# DISE_O_CON_3_3_Y_5_spi_separado_y_diodos.net
KiCad netlist of a schematic drawn in Altium Designer
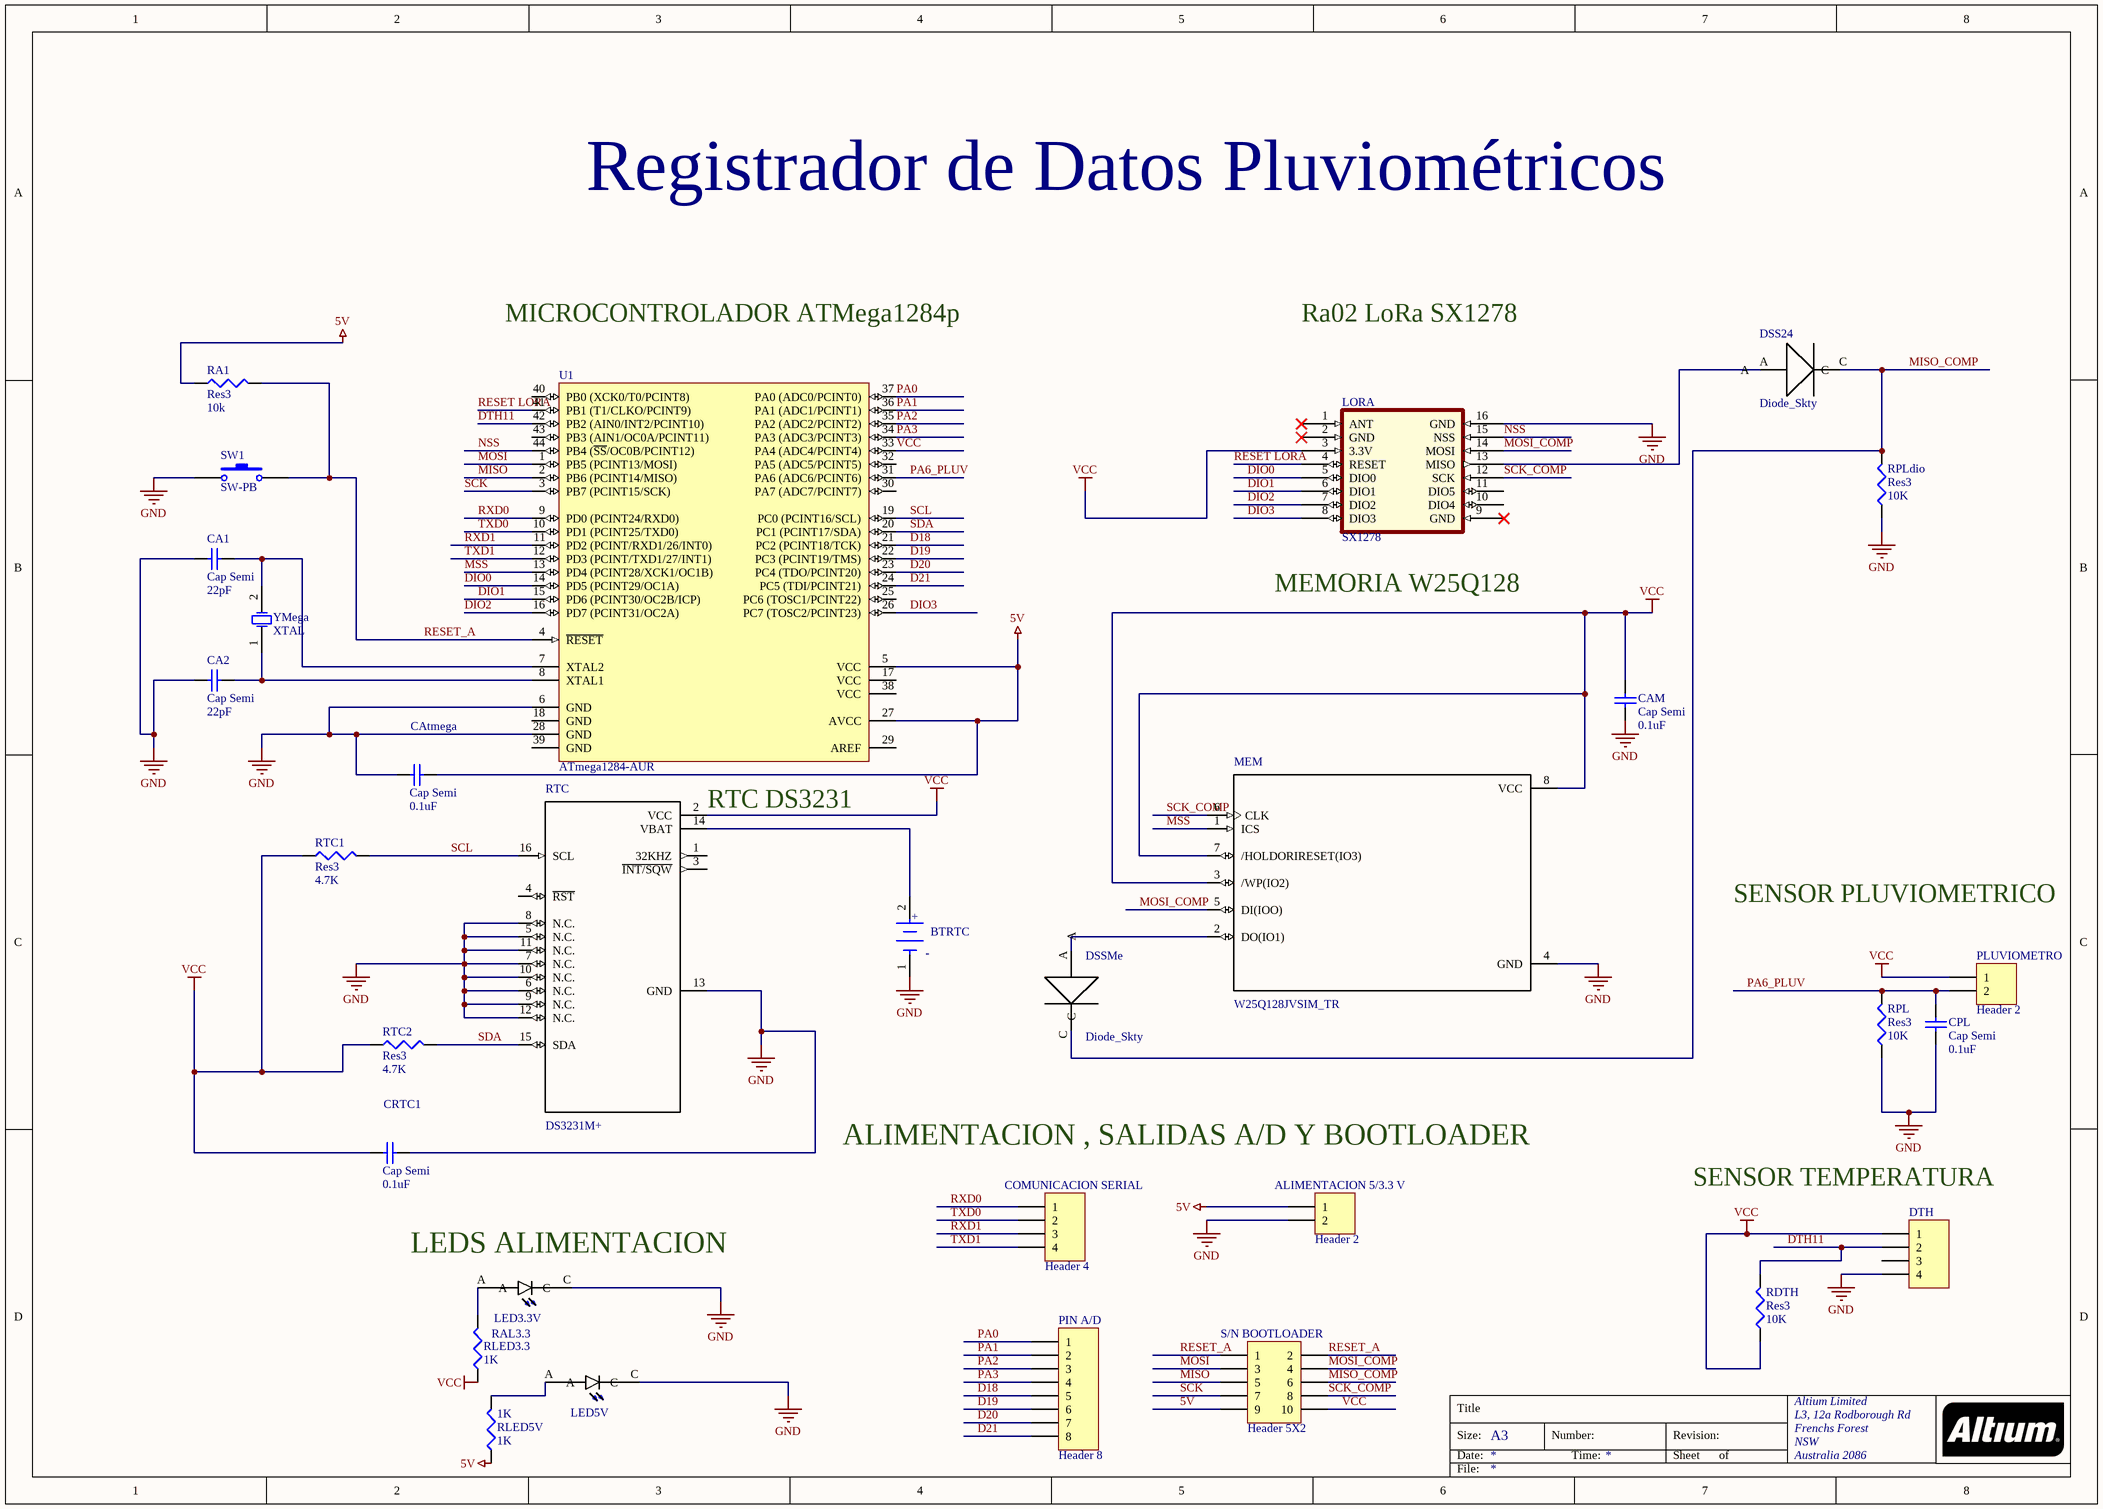
[diagram p0: DISEÑO CON 3.3 Y 5 spi separado y diodos.SchDoc]

(export (version "E")
  (design (tool "Eeschema 10.0.6"))
  (components
    (comp (ref "1K")
      (value "RLED5V")
      (footprint "6-0805_L")
      (description "Resistor")
      (fields (field (name "ALTIUM_VALUE") "1K") (field (name "PUBLISHER") "Altium Limited"))
      (libsource (lib "Miscellaneous Devices") (part "Res3"))
    )
    (comp (ref "ALIMENTACION 5/3.3 V")
      (value "Header 2")
      (footprint "HDR1X2")
      (description "Header, 2-Pin")
      (fields (field (name "PUBLISHER") "Altium Limited"))
      (libsource (lib "Miscellaneous Connectors") (part "Header 2"))
    )
    (comp (ref "BTRTC")
      (value "CR-1220-HFN")
      (footprint "Panasonic_CR-1220-HFN_MFG")
      (libsource (lib "Batt_Panasonic_CR-1220-HFN_eec") (part "CR-1220-HFN"))
    )
    (comp (ref "CA1")
      (value "Cap Semi")
      (footprint "C0805")
      (description "Capacitor (Semiconductor SIM Model)")
      (fields (field (name "ALTIUM_VALUE") "22pF") (field (name "PUBLISHER") "Altium Limited"))
      (libsource (lib "Miscellaneous Devices") (part "Cap Semi"))
    )
    (comp (ref "CA2")
      (value "Cap Semi")
      (footprint "C0805")
      (description "Capacitor (Semiconductor SIM Model)")
      (fields (field (name "ALTIUM_VALUE") "22pF") (field (name "PUBLISHER") "Altium Limited"))
      (libsource (lib "Miscellaneous Devices") (part "Cap Semi"))
    )
    (comp (ref "CAM")
      (value "Cap Semi")
      (footprint "C0805")
      (description "Capacitor (Semiconductor SIM Model)")
      (fields (field (name "ALTIUM_VALUE") "0.1uF") (field (name "PUBLISHER") "Altium Limited"))
      (libsource (lib "Miscellaneous Devices") (part "Cap Semi"))
    )
    (comp (ref "CAtmega")
      (value "Cap Semi")
      (footprint "C0805")
      (description "Capacitor (Semiconductor SIM Model)")
      (fields (field (name "ALTIUM_VALUE") "0.1uF") (field (name "PUBLISHER") "Altium Limited"))
      (libsource (lib "Miscellaneous Devices") (part "Cap Semi"))
    )
    (comp (ref "COMUNICACION SERIAL")
      (value "Header 4")
      (footprint "HDR1X4")
      (description "Header, 4-Pin")
      (fields (field (name "PUBLISHER") "Altium Limited"))
      (libsource (lib "Miscellaneous Connectors") (part "Header 4"))
    )
    (comp (ref "CPL")
      (value "Cap Semi")
      (footprint "C0805")
      (description "Capacitor (Semiconductor SIM Model)")
      (fields (field (name "ALTIUM_VALUE") "0.1uF") (field (name "PUBLISHER") "Altium Limited"))
      (libsource (lib "Miscellaneous Devices") (part "Cap Semi"))
    )
    (comp (ref "CRTC1")
      (value "Cap Semi")
      (footprint "C0805")
      (description "Capacitor (Semiconductor SIM Model)")
      (fields (field (name "ALTIUM_VALUE") "0.1uF") (field (name "PUBLISHER") "Altium Limited"))
      (libsource (lib "Miscellaneous Devices") (part "Cap Semi"))
    )
    (comp (ref "DSS24")
      (value "Diode_Skty")
      (footprint "*DIOM5436X247N")
      (libsource (lib "SS24_Real") (part "Component_1"))
    )
    (comp (ref "DSSMe")
      (value "Diode_Skty")
      (footprint "*DIOM5436X247N")
      (libsource (lib "SS24_Real") (part "Component_1"))
    )
    (comp (ref "DTH")
      (value "~")
      (footprint "HDR1X4")
      (description "Header, 4-Pin")
      (fields (field (name "PUBLISHER") "Altium Limited"))
      (libsource (lib "Miscellaneous Connectors") (part "Header 4"))
    )
    (comp (ref "LED3.3V")
      (value "~")
      (footprint "*LEDC2012X70N_598-8140-107F(Primary)")
      (description "Led; 0805 Smt Led, Yellow, Alingap, Water Clear Lens, 140 Deg Viewing Angle")
      (fields (field (name "MP") "598-8140-107F") (field (name "MF") "Dialight"))
      (libsource (lib "598-8140-107F") (part "598-8140-107F"))
    )
    (comp (ref "LED5V")
      (value "~")
      (footprint "*LEDC2012X70N_598-8140-107F(Primary)")
      (description "Led; 0805 Smt Led, Yellow, Alingap, Water Clear Lens, 140 Deg Viewing Angle")
      (fields (field (name "MP") "598-8140-107F") (field (name "MF") "Dialight"))
      (libsource (lib "598-8140-107F") (part "598-8140-107F"))
    )
    (comp (ref "LORA")
      (value "SX1278")
      (footprint "SOP200P1800X250-16N")
      (libsource (lib "LORA") (part "Component_1"))
    )
    (comp (ref "MEM")
      (value "W25Q128JVSIM_TR")
      (footprint "*SOIC127P790X216-8N")
      (description "Ic Flash 128mbit 133mhz 8soic")
      (fields (field (name "MP") "W25Q128JVSIM TR") (field (name "MF") "Winbond Electronics"))
      (libsource (lib "W25Q128JVSIM_TR") (part "W25Q128JVSIM_TR"))
    )
    (comp (ref "PIN A/D")
      (value "Header 8")
      (footprint "HDR1X8")
      (description "Header, 8-Pin")
      (fields (field (name "PUBLISHER") "Altium Limited"))
      (libsource (lib "Miscellaneous Connectors") (part "Header 8"))
    )
    (comp (ref "PLUVIOMETRO")
      (value "Header 2")
      (footprint "HDR1X2")
      (description "Header, 2-Pin")
      (fields (field (name "PUBLISHER") "Altium Limited"))
      (libsource (lib "Miscellaneous Connectors") (part "Header 2"))
    )
    (comp (ref "RA1")
      (value "Res3")
      (footprint "6-0805_L")
      (description "Resistor")
      (fields (field (name "ALTIUM_VALUE") "10k") (field (name "PUBLISHER") "Altium Limited"))
      (libsource (lib "Miscellaneous Devices") (part "Res3"))
    )
    (comp (ref "RAL3.3")
      (value "RLED3.3")
      (footprint "6-0805_L")
      (description "Resistor")
      (fields (field (name "ALTIUM_VALUE") "1K") (field (name "PUBLISHER") "Altium Limited"))
      (libsource (lib "Miscellaneous Devices") (part "Res3"))
    )
    (comp (ref "RDTH")
      (value "Res3")
      (footprint "6-0805_L")
      (description "Resistor")
      (fields (field (name "ALTIUM_VALUE") "10K") (field (name "PUBLISHER") "Altium Limited"))
      (libsource (lib "Miscellaneous Devices") (part "Res3"))
    )
    (comp (ref "RPL")
      (value "Res3")
      (footprint "6-0805_L")
      (description "Resistor")
      (fields (field (name "ALTIUM_VALUE") "10K") (field (name "PUBLISHER") "Altium Limited"))
      (libsource (lib "Miscellaneous Devices") (part "Res3"))
    )
    (comp (ref "RPLdio")
      (value "Res3")
      (footprint "6-0805_L")
      (description "Resistor")
      (fields (field (name "ALTIUM_VALUE") "10K") (field (name "PUBLISHER") "Altium Limited"))
      (libsource (lib "Miscellaneous Devices") (part "Res3"))
    )
    (comp (ref "RTC")
      (value "DS3231M+")
      (footprint "*SOIC127P1032X265-16N")
      (description "Ic Real Time Clock I2c 16soic - Ds3231m+")
      (fields (field (name "MF") "Maxim Integrated"))
      (libsource (lib "DS3231M_") (part "DS3231M+"))
    )
    (comp (ref "RTC1")
      (value "Res3")
      (footprint "6-0805_L")
      (description "Resistor")
      (fields (field (name "ALTIUM_VALUE") "4.7K") (field (name "PUBLISHER") "Altium Limited"))
      (libsource (lib "Miscellaneous Devices") (part "Res3"))
    )
    (comp (ref "RTC2")
      (value "Res3")
      (footprint "6-0805_L")
      (description "Resistor")
      (fields (field (name "ALTIUM_VALUE") "4.7K") (field (name "PUBLISHER") "Altium Limited"))
      (libsource (lib "Miscellaneous Devices") (part "Res3"))
    )
    (comp (ref "S/N BOOTLOADER")
      (value "Header 5X2")
      (footprint "HDR2X5")
      (description "Header, 5-Pin, Dual row")
      (fields (field (name "PUBLISHER") "Altium Limited"))
      (libsource (lib "Miscellaneous Connectors") (part "Header 5X2"))
    )
    (comp (ref "SW1")
      (value "SW-PB")
      (footprint "SPST-2")
      (description "Switch")
      (fields (field (name "PUBLISHER") "Altium Limited"))
      (libsource (lib "Miscellaneous Devices") (part "SW-PB"))
    )
    (comp (ref "U1")
      (value "ATmega1284-AUR")
      (footprint "44A_N")
      (fields (field (name "PUBLISHER") "Altium Limited"))
      (libsource (lib "Atmel Microcontroller 8-Bit megaAVR") (part "ATmega1284-AUR"))
    )
    (comp (ref "YMega")
      (value "XTAL")
      (footprint "R38")
      (description "Crystal Oscillator")
      (fields (field (name "PUBLISHER") "Altium Limited"))
      (libsource (lib "Miscellaneous Devices") (part "XTAL"))
    )
  )
  (nets
    (net (code "1") (name "/D18") (class "Default")
      (node (ref "PIN A/D") (pin "5") (pinfunction "5_5") (pintype "passive"))
      (node (ref "U1") (pin "21") (pinfunction "PC2_(PCINT18/TCK)_21") (pintype "bidirectional"))
    )
    (net (code "2") (name "/D19") (class "Default")
      (node (ref "PIN A/D") (pin "6") (pinfunction "6_6") (pintype "passive"))
      (node (ref "U1") (pin "22") (pinfunction "PC3_(PCINT19/TMS)_22") (pintype "bidirectional"))
    )
    (net (code "3") (name "/D20") (class "Default")
      (node (ref "PIN A/D") (pin "7") (pinfunction "7_7") (pintype "passive"))
      (node (ref "U1") (pin "23") (pinfunction "PC4_(TDO/PCINT20)_23") (pintype "bidirectional"))
    )
    (net (code "4") (name "/D21") (class "Default")
      (node (ref "PIN A/D") (pin "8") (pinfunction "8_8") (pintype "passive"))
      (node (ref "U1") (pin "24") (pinfunction "PC5_(TDI/PCINT21)_24") (pintype "bidirectional"))
    )
    (net (code "5") (name "/DIO0") (class "Default")
      (node (ref "LORA") (pin "5") (pinfunction "DIO0_5") (pintype "bidirectional"))
      (node (ref "U1") (pin "14") (pinfunction "PD5_(PCINT29/OC1A)_14") (pintype "bidirectional"))
    )
    (net (code "6") (name "/DIO1") (class "Default")
      (node (ref "LORA") (pin "6") (pinfunction "DIO1_6") (pintype "bidirectional"))
      (node (ref "U1") (pin "15") (pinfunction "PD6_(PCINT30/OC2B/ICP)_15") (pintype "bidirectional"))
    )
    (net (code "7") (name "/DIO2") (class "Default")
      (node (ref "LORA") (pin "7") (pinfunction "DIO2_7") (pintype "bidirectional"))
      (node (ref "U1") (pin "16") (pinfunction "PD7_(PCINT31/OC2A)_16") (pintype "bidirectional"))
    )
    (net (code "8") (name "/DIO3") (class "Default")
      (node (ref "LORA") (pin "8") (pinfunction "DIO3_8") (pintype "bidirectional"))
      (node (ref "U1") (pin "26") (pinfunction "PC7_(TOSC2/PCINT23)_26") (pintype "bidirectional"))
    )
    (net (code "9") (name "/DTH11") (class "Default")
      (node (ref "DTH") (pin "2") (pinfunction "2_2") (pintype "passive"))
      (node (ref "RDTH") (pin "2") (pinfunction "2_2") (pintype "passive"))
      (node (ref "U1") (pin "42") (pinfunction "PB2_(AIN0/INT2/PCINT10)_42") (pintype "bidirectional"))
    )
    (net (code "10") (name "/MISO") (class "Default")
      (node (ref "S/N BOOTLOADER") (pin "5") (pinfunction "5_5") (pintype "passive"))
      (node (ref "U1") (pin "2") (pinfunction "PB6_(PCINT14/MISO)_2") (pintype "bidirectional"))
    )
    (net (code "11") (name "/MISO_COMP") (class "Default")
      (node (ref "DSS24") (pin "C") (pinfunction "C_C") (pintype "passive"))
      (node (ref "DSSMe") (pin "C") (pinfunction "C_C") (pintype "passive"))
      (node (ref "RPLdio") (pin "2") (pinfunction "2_2") (pintype "passive"))
      (node (ref "S/N BOOTLOADER") (pin "6") (pinfunction "6_6") (pintype "passive"))
    )
    (net (code "12") (name "/MOSI") (class "Default")
      (node (ref "S/N BOOTLOADER") (pin "3") (pinfunction "3_3") (pintype "passive"))
      (node (ref "U1") (pin "1") (pinfunction "PB5_(PCINT13/MOSI)_1") (pintype "bidirectional"))
    )
    (net (code "13") (name "/MOSI_COMP") (class "Default")
      (node (ref "LORA") (pin "14") (pinfunction "MOSI_14") (pintype "input"))
      (node (ref "MEM") (pin "5") (pinfunction "DI(IOO)_5") (pintype "bidirectional"))
      (node (ref "S/N BOOTLOADER") (pin "4") (pinfunction "4_4") (pintype "passive"))
    )
    (net (code "14") (name "/MSS") (class "Default")
      (node (ref "MEM") (pin "1") (pinfunction "ICS_1") (pintype "input"))
      (node (ref "U1") (pin "13") (pinfunction "PD4_(PCINT28/XCK1/OC1B)_13") (pintype "bidirectional"))
    )
    (net (code "15") (name "/NSS") (class "Default")
      (node (ref "LORA") (pin "15") (pinfunction "NSS_15") (pintype "input"))
      (node (ref "U1") (pin "44") (pinfunction "PB4_(~{SS}/OC0B/PCINT12)_44") (pintype "bidirectional"))
    )
    (net (code "16") (name "/PA0") (class "Default")
      (node (ref "PIN A/D") (pin "1") (pinfunction "1_1") (pintype "passive"))
      (node (ref "U1") (pin "37") (pinfunction "PA0_(ADC0/PCINT0)_37") (pintype "bidirectional"))
    )
    (net (code "17") (name "/PA1") (class "Default")
      (node (ref "PIN A/D") (pin "2") (pinfunction "2_2") (pintype "passive"))
      (node (ref "U1") (pin "36") (pinfunction "PA1_(ADC1/PCINT1)_36") (pintype "bidirectional"))
    )
    (net (code "18") (name "/PA2") (class "Default")
      (node (ref "PIN A/D") (pin "3") (pinfunction "3_3") (pintype "passive"))
      (node (ref "U1") (pin "35") (pinfunction "PA2_(ADC2/PCINT2)_35") (pintype "bidirectional"))
    )
    (net (code "19") (name "/PA3") (class "Default")
      (node (ref "PIN A/D") (pin "4") (pinfunction "4_4") (pintype "passive"))
      (node (ref "U1") (pin "34") (pinfunction "PA3_(ADC3/PCINT3)_34") (pintype "bidirectional"))
    )
    (net (code "20") (name "/PA6_PLUV") (class "Default")
      (node (ref "CPL") (pin "2") (pinfunction "2_2") (pintype "passive"))
      (node (ref "PLUVIOMETRO") (pin "2") (pinfunction "2_2") (pintype "passive"))
      (node (ref "RPL") (pin "2") (pinfunction "2_2") (pintype "passive"))
      (node (ref "U1") (pin "31") (pinfunction "PA6_(ADC6/PCINT6)_31") (pintype "bidirectional"))
    )
    (net (code "21") (name "/RESET LORA") (class "Default")
      (node (ref "LORA") (pin "4") (pinfunction "RESET_4") (pintype "bidirectional"))
      (node (ref "U1") (pin "41") (pinfunction "PB1_(T1/CLKO/PCINT9)_41") (pintype "bidirectional"))
    )
    (net (code "22") (name "/RESET_A") (class "Default")
      (node (ref "RA1") (pin "2") (pinfunction "2_2") (pintype "passive"))
      (node (ref "S/N BOOTLOADER") (pin "1") (pinfunction "1_1") (pintype "passive"))
      (node (ref "S/N BOOTLOADER") (pin "2") (pinfunction "2_2") (pintype "passive"))
      (node (ref "SW1") (pin "2") (pinfunction "2_2") (pintype "passive"))
      (node (ref "U1") (pin "4") (pinfunction "~{RESET}_4") (pintype "input"))
    )
    (net (code "23") (name "/RXD0") (class "Default")
      (node (ref "COMUNICACION SERIAL") (pin "1") (pinfunction "1_1") (pintype "passive"))
      (node (ref "U1") (pin "9") (pinfunction "PD0_(PCINT24/RXD0)_9") (pintype "bidirectional"))
    )
    (net (code "24") (name "/RXD1") (class "Default")
      (node (ref "COMUNICACION SERIAL") (pin "3") (pinfunction "3_3") (pintype "passive"))
      (node (ref "U1") (pin "11") (pinfunction "PD2_(PCINT/RXD1/26/INT0)_11") (pintype "bidirectional"))
    )
    (net (code "25") (name "/SCK") (class "Default")
      (node (ref "S/N BOOTLOADER") (pin "7") (pinfunction "7_7") (pintype "passive"))
      (node (ref "U1") (pin "3") (pinfunction "PB7_(PCINT15/SCK)_3") (pintype "bidirectional"))
    )
    (net (code "26") (name "/SCK_COMP") (class "Default")
      (node (ref "LORA") (pin "12") (pinfunction "SCK_12") (pintype "input"))
      (node (ref "MEM") (pin "6") (pinfunction "CLK_6") (pintype "input"))
      (node (ref "S/N BOOTLOADER") (pin "8") (pinfunction "8_8") (pintype "passive"))
    )
    (net (code "27") (name "/SCL") (class "Default")
      (node (ref "RTC") (pin "16") (pinfunction "SCL_16") (pintype "input"))
      (node (ref "RTC1") (pin "2") (pinfunction "2_2") (pintype "passive"))
      (node (ref "U1") (pin "19") (pinfunction "PC0_(PCINT16/SCL)_19") (pintype "bidirectional"))
    )
    (net (code "28") (name "/SDA") (class "Default")
      (node (ref "RTC") (pin "15") (pinfunction "SDA_15") (pintype "bidirectional"))
      (node (ref "RTC2") (pin "2") (pinfunction "2_2") (pintype "passive"))
      (node (ref "U1") (pin "20") (pinfunction "PC1_(PCINT17/SDA)_20") (pintype "bidirectional"))
    )
    (net (code "29") (name "/TXD0") (class "Default")
      (node (ref "COMUNICACION SERIAL") (pin "2") (pinfunction "2_2") (pintype "passive"))
      (node (ref "U1") (pin "10") (pinfunction "PD1_(PCINT25/TXD0)_10") (pintype "bidirectional"))
    )
    (net (code "30") (name "/TXD1") (class "Default")
      (node (ref "COMUNICACION SERIAL") (pin "4") (pinfunction "4_4") (pintype "passive"))
      (node (ref "U1") (pin "12") (pinfunction "PD3_(PCINT/TXD1/27/INT1)_12") (pintype "bidirectional"))
    )
    (net (code "31") (name "5V") (class "Default")
      (node (ref "1K") (pin "1") (pinfunction "1_1") (pintype "passive"))
      (node (ref "ALIMENTACION 5/3.3 V") (pin "1") (pinfunction "1_1") (pintype "passive"))
      (node (ref "CAtmega") (pin "2") (pinfunction "2_2") (pintype "passive"))
      (node (ref "RA1") (pin "1") (pinfunction "1_1") (pintype "passive"))
      (node (ref "S/N BOOTLOADER") (pin "9") (pinfunction "9_9") (pintype "passive"))
      (node (ref "U1") (pin "27") (pinfunction "AVCC_27") (pintype "power_in"))
      (node (ref "U1") (pin "5") (pinfunction "VCC_5") (pintype "power_in"))
    )
    (net (code "32") (name "GND") (class "Default")
      (node (ref "ALIMENTACION 5/3.3 V") (pin "2") (pinfunction "2_2") (pintype "passive"))
      (node (ref "BTRTC") (pin "1") (pinfunction "C_1") (pintype "passive"))
      (node (ref "CA1") (pin "1") (pinfunction "1_1") (pintype "passive"))
      (node (ref "CA2") (pin "1") (pinfunction "1_1") (pintype "passive"))
      (node (ref "CAM") (pin "1") (pinfunction "1_1") (pintype "passive"))
      (node (ref "CAtmega") (pin "1") (pinfunction "1_1") (pintype "passive"))
      (node (ref "CPL") (pin "1") (pinfunction "1_1") (pintype "passive"))
      (node (ref "CRTC1") (pin "2") (pinfunction "2_2") (pintype "passive"))
      (node (ref "DTH") (pin "4") (pinfunction "4_4") (pintype "passive"))
      (node (ref "LED3.3V") (pin "C") (pinfunction "C_C") (pintype "passive"))
      (node (ref "LED5V") (pin "C") (pinfunction "C_C") (pintype "passive"))
      (node (ref "LORA") (pin "16") (pinfunction "GND_16") (pintype "input"))
      (node (ref "MEM") (pin "4") (pinfunction "GND_4") (pintype "power_in"))
      (node (ref "RPL") (pin "1") (pinfunction "1_1") (pintype "passive"))
      (node (ref "RPLdio") (pin "1") (pinfunction "1_1") (pintype "passive"))
      (node (ref "RTC") (pin "10") (pinfunction "N.C._10") (pintype "bidirectional"))
      (node (ref "RTC") (pin "11") (pinfunction "N.C._11") (pintype "bidirectional"))
      (node (ref "RTC") (pin "12") (pinfunction "N.C._12") (pintype "bidirectional"))
      (node (ref "RTC") (pin "13") (pinfunction "GND_13") (pintype "power_in"))
      (node (ref "RTC") (pin "5") (pinfunction "N.C._5") (pintype "bidirectional"))
      (node (ref "RTC") (pin "6") (pinfunction "N.C._6") (pintype "bidirectional"))
      (node (ref "RTC") (pin "7") (pinfunction "N.C._7") (pintype "bidirectional"))
      (node (ref "RTC") (pin "8") (pinfunction "N.C._8") (pintype "bidirectional"))
      (node (ref "RTC") (pin "9") (pinfunction "N.C._9") (pintype "bidirectional"))
      (node (ref "SW1") (pin "1") (pinfunction "1_1") (pintype "passive"))
      (node (ref "U1") (pin "28") (pinfunction "GND_28") (pintype "power_in"))
      (node (ref "U1") (pin "6") (pinfunction "GND_6") (pintype "power_in"))
    )
    (net (code "33") (name "Net-(1K-Pad2)") (class "Default")
      (node (ref "1K") (pin "2") (pinfunction "2_2") (pintype "passive"))
      (node (ref "LED5V") (pin "A") (pinfunction "A_A") (pintype "passive"))
    )
    (net (code "34") (name "Net-(BTRTC-A)") (class "Default")
      (node (ref "BTRTC") (pin "2") (pinfunction "A_2") (pintype "passive"))
      (node (ref "RTC") (pin "14") (pinfunction "VBAT_14") (pintype "power_in"))
    )
    (net (code "35") (name "Net-(LED3.3V-PadA)") (class "Default")
      (node (ref "LED3.3V") (pin "A") (pinfunction "A_A") (pintype "passive"))
      (node (ref "RAL3.3") (pin "2") (pinfunction "2_2") (pintype "passive"))
    )
    (net (code "36") (name "Net-(LORA-MISO)") (class "Default")
      (node (ref "DSS24") (pin "A") (pinfunction "A_A") (pintype "passive"))
      (node (ref "LORA") (pin "13") (pinfunction "MISO_13") (pintype "output"))
    )
    (net (code "37") (name "Net-(MEM-DO(IO1))") (class "Default")
      (node (ref "DSSMe") (pin "A") (pinfunction "A_A") (pintype "passive"))
      (node (ref "MEM") (pin "2") (pinfunction "DO(IO1)_2") (pintype "bidirectional"))
    )
    (net (code "38") (name "Net-(U1-XTAL1)") (class "Default")
      (node (ref "CA2") (pin "2") (pinfunction "2_2") (pintype "passive"))
      (node (ref "U1") (pin "8") (pinfunction "XTAL1_8") (pintype "passive"))
      (node (ref "YMega") (pin "1") (pinfunction "OSC1_1") (pintype "passive"))
    )
    (net (code "39") (name "Net-(U1-XTAL2)") (class "Default")
      (node (ref "CA1") (pin "2") (pinfunction "2_2") (pintype "passive"))
      (node (ref "U1") (pin "7") (pinfunction "XTAL2_7") (pintype "passive"))
      (node (ref "YMega") (pin "2") (pinfunction "OSC2_2") (pintype "passive"))
    )
    (net (code "40") (name "VCC") (class "Default")
      (node (ref "CAM") (pin "2") (pinfunction "2_2") (pintype "passive"))
      (node (ref "CRTC1") (pin "1") (pinfunction "1_1") (pintype "passive"))
      (node (ref "DTH") (pin "1") (pinfunction "1_1") (pintype "passive"))
      (node (ref "LORA") (pin "3") (pinfunction "3.3V_3") (pintype "input"))
      (node (ref "MEM") (pin "3") (pinfunction "/WP(IO2)_3") (pintype "bidirectional"))
      (node (ref "MEM") (pin "7") (pinfunction "/HOLDORIRESET(IO3)_7") (pintype "bidirectional"))
      (node (ref "MEM") (pin "8") (pinfunction "VCC_8") (pintype "power_in"))
      (node (ref "PLUVIOMETRO") (pin "1") (pinfunction "1_1") (pintype "passive"))
      (node (ref "RAL3.3") (pin "1") (pinfunction "1_1") (pintype "passive"))
      (node (ref "RDTH") (pin "1") (pinfunction "1_1") (pintype "passive"))
      (node (ref "RTC") (pin "2") (pinfunction "VCC_2") (pintype "power_in"))
      (node (ref "RTC1") (pin "1") (pinfunction "1_1") (pintype "passive"))
      (node (ref "RTC2") (pin "1") (pinfunction "1_1") (pintype "passive"))
      (node (ref "S/N BOOTLOADER") (pin "10") (pinfunction "10_10") (pintype "passive"))
      (node (ref "U1") (pin "33") (pinfunction "PA4_(ADC4/PCINT4)_33") (pintype "bidirectional"))
    )
    (net (code "41") (name "unconnected-(DTH-Pad3)") (class "Default")
      (node (ref "DTH") (pin "3") (pinfunction "3_3") (pintype "passive"))
    )
    (net (code "42") (name "unconnected-(LORA-ANT-Pad1)") (class "Default")
      (node (ref "LORA") (pin "1") (pinfunction "ANT_1") (pintype "input+no_connect"))
    )
    (net (code "43") (name "unconnected-(LORA-DIO4-Pad10)") (class "Default")
      (node (ref "LORA") (pin "10") (pinfunction "DIO4_10") (pintype "bidirectional"))
    )
    (net (code "44") (name "unconnected-(LORA-DIO5-Pad11)") (class "Default")
      (node (ref "LORA") (pin "11") (pinfunction "DIO5_11") (pintype "bidirectional"))
    )
    (net (code "45") (name "unconnected-(LORA-GND-Pad2)") (class "Default")
      (node (ref "LORA") (pin "2") (pinfunction "GND_2") (pintype "input+no_connect"))
    )
    (net (code "46") (name "unconnected-(LORA-GND-Pad9)") (class "Default")
      (node (ref "LORA") (pin "9") (pinfunction "GND_9") (pintype "input+no_connect"))
    )
    (net (code "47") (name "unconnected-(RTC-32KHZ-Pad1)") (class "Default")
      (node (ref "RTC") (pin "1") (pinfunction "32KHZ_1") (pintype "output"))
    )
    (net (code "48") (name "unconnected-(RTC-~{INT{slash}SQW}-Pad3)") (class "Default")
      (node (ref "RTC") (pin "3") (pinfunction "~{INT/SQW}_3") (pintype "output"))
    )
    (net (code "49") (name "unconnected-(RTC-~{RST}-Pad4)") (class "Default")
      (node (ref "RTC") (pin "4") (pinfunction "~{RST}_4") (pintype "bidirectional"))
    )
    (net (code "50") (name "unconnected-(U1-AREF-Pad29)") (class "Default")
      (node (ref "U1") (pin "29") (pinfunction "AREF_29") (pintype "power_in"))
    )
    (net (code "51") (name "unconnected-(U1-GND-Pad18)") (class "Default")
      (node (ref "U1") (pin "18") (pinfunction "GND_18") (pintype "power_in"))
    )
    (net (code "52") (name "unconnected-(U1-GND-Pad39)") (class "Default")
      (node (ref "U1") (pin "39") (pinfunction "GND_39") (pintype "power_in"))
    )
    (net (code "53") (name "unconnected-(U1-PA5_(ADC5{slash}PCINT5)-Pad32)") (class "Default")
      (node (ref "U1") (pin "32") (pinfunction "PA5_(ADC5/PCINT5)_32") (pintype "bidirectional"))
    )
    (net (code "54") (name "unconnected-(U1-PA7_(ADC7{slash}PCINT7)-Pad30)") (class "Default")
      (node (ref "U1") (pin "30") (pinfunction "PA7_(ADC7/PCINT7)_30") (pintype "bidirectional"))
    )
    (net (code "55") (name "unconnected-(U1-PB0_(XCK0{slash}T0{slash}PCINT8)-Pad40)") (class "Default")
      (node (ref "U1") (pin "40") (pinfunction "PB0_(XCK0/T0/PCINT8)_40") (pintype "bidirectional"))
    )
    (net (code "56") (name "unconnected-(U1-PB3_(AIN1{slash}OC0A{slash}PCINT11)-Pad43)") (class "Default")
      (node (ref "U1") (pin "43") (pinfunction "PB3_(AIN1/OC0A/PCINT11)_43") (pintype "bidirectional"))
    )
    (net (code "57") (name "unconnected-(U1-PC6_(TOSC1{slash}PCINT22)-Pad25)") (class "Default")
      (node (ref "U1") (pin "25") (pinfunction "PC6_(TOSC1/PCINT22)_25") (pintype "bidirectional"))
    )
    (net (code "58") (name "unconnected-(U1-VCC-Pad17)") (class "Default")
      (node (ref "U1") (pin "17") (pinfunction "VCC_17") (pintype "power_in"))
    )
    (net (code "59") (name "unconnected-(U1-VCC-Pad38)") (class "Default")
      (node (ref "U1") (pin "38") (pinfunction "VCC_38") (pintype "power_in"))
    )
  )
)
